# basic.net
KiCad netlist of a schematic drawn in EAGLE
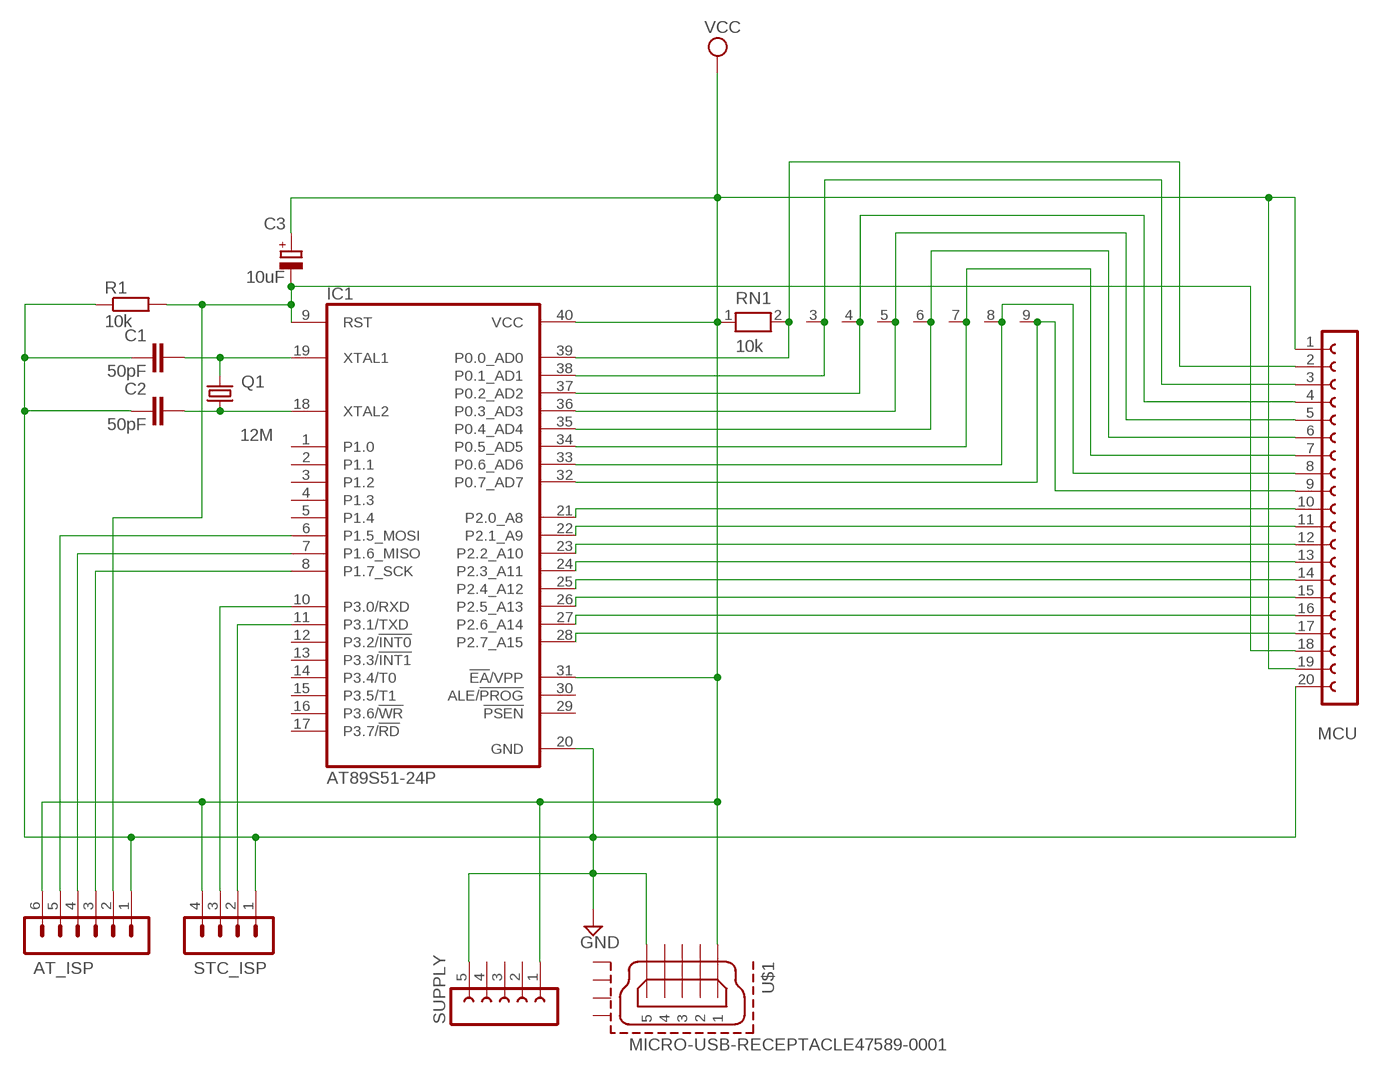
[diagram p0: schematic, sheet 1]

(export (version "E")
  (design (tool "Eeschema 10.0.6"))
  (components
    (comp (ref "AT_ISP")
      (value "MA06-1")
      (footprint "eagle-import:MA06-1")
      (libsource (lib "eagle-import") (part "MA06-1"))
    )
    (comp (ref "C1")
      (value "50pF")
      (footprint "eagle-import:C050-025X075")
      (libsource (lib "eagle-import") (part "C-EU050-025X075"))
    )
    (comp (ref "C2")
      (value "50pF")
      (footprint "eagle-import:C050-025X075")
      (libsource (lib "eagle-import") (part "C-EU050-025X075"))
    )
    (comp (ref "C3")
      (value "10uF")
      (footprint "eagle-import:E2,5-6")
      (libsource (lib "eagle-import") (part "CPOL-EUE2.5-6"))
    )
    (comp (ref "IC1")
      (value "AT89S51-24P")
      (footprint "eagle-import:DIL40")
      (fields (field (name "MPN") "AT89S51-24PU"))
      (libsource (lib "eagle-import") (part "AT89S51-P24"))
    )
    (comp (ref "MCU")
      (value "FE20-1")
      (footprint "eagle-import:FE20")
      (libsource (lib "eagle-import") (part "FE20-1"))
    )
    (comp (ref "Q1")
      (value "12M")
      (footprint "eagle-import:HC49U70")
      (libsource (lib "eagle-import") (part "CRYSTALHC49U70"))
    )
    (comp (ref "R1")
      (value "10k")
      (footprint "eagle-import:0207_10")
      (libsource (lib "eagle-import") (part "R-EU_0207/10"))
    )
    (comp (ref "RN1")
      (value "10k")
      (footprint "eagle-import:RN-9")
      (libsource (lib "eagle-import") (part "RN08"))
    )
    (comp (ref "STC_ISP")
      (value "MA04-1")
      (footprint "eagle-import:MA04-1")
      (libsource (lib "eagle-import") (part "MA04-1"))
    )
    (comp (ref "SUPPLY")
      (value "FE05-1")
      (footprint "eagle-import:FE05-1")
      (libsource (lib "eagle-import") (part "FE05-1"))
    )
    (comp (ref "U$1")
      (value "MICRO-USB-RECEPTACLE47589-0001")
      (footprint "eagle-import:47589-0001")
      (libsource (lib "eagle-import") (part "MICRO-USB-RECEPTACLE47589-0001"))
    )
  )
  (nets
    (net (code "1") (name "GND") (class "Default")
      (node (ref "AT_ISP") (pin "1") (pinfunction "1_1") (pintype "passive"))
      (node (ref "C1") (pin "1") (pinfunction "1_1") (pintype "passive"))
      (node (ref "C2") (pin "1") (pinfunction "1_1") (pintype "passive"))
      (node (ref "IC1") (pin "20") (pinfunction "GND_20") (pintype "power_in"))
      (node (ref "MCU") (pin "20") (pinfunction "20_20") (pintype "passive"))
      (node (ref "R1") (pin "1") (pinfunction "1_1") (pintype "passive"))
      (node (ref "STC_ISP") (pin "1") (pinfunction "1_1") (pintype "passive"))
      (node (ref "SUPPLY") (pin "5") (pinfunction "5_5") (pintype "passive"))
      (node (ref "U$1") (pin "5") (pinfunction "5_5") (pintype "input"))
    )
    (net (code "2") (name "Net-(IC1-P0.0_AD0)") (class "Default")
      (node (ref "IC1") (pin "39") (pinfunction "P0.0_AD0_39") (pintype "bidirectional"))
      (node (ref "MCU") (pin "2") (pinfunction "2_2") (pintype "passive"))
      (node (ref "RN1") (pin "2") (pinfunction "2_2") (pintype "passive"))
    )
    (net (code "3") (name "Net-(IC1-P0.1_AD1)") (class "Default")
      (node (ref "IC1") (pin "38") (pinfunction "P0.1_AD1_38") (pintype "bidirectional"))
      (node (ref "MCU") (pin "3") (pinfunction "3_3") (pintype "passive"))
      (node (ref "RN1") (pin "3") (pinfunction "3_3") (pintype "passive"))
    )
    (net (code "4") (name "Net-(IC1-P0.2_AD2)") (class "Default")
      (node (ref "IC1") (pin "37") (pinfunction "P0.2_AD2_37") (pintype "bidirectional"))
      (node (ref "MCU") (pin "4") (pinfunction "4_4") (pintype "passive"))
      (node (ref "RN1") (pin "4") (pinfunction "4_4") (pintype "passive"))
    )
    (net (code "5") (name "Net-(IC1-P0.3_AD3)") (class "Default")
      (node (ref "IC1") (pin "36") (pinfunction "P0.3_AD3_36") (pintype "bidirectional"))
      (node (ref "MCU") (pin "5") (pinfunction "5_5") (pintype "passive"))
      (node (ref "RN1") (pin "5") (pinfunction "5_5") (pintype "passive"))
    )
    (net (code "6") (name "Net-(IC1-P0.4_AD4)") (class "Default")
      (node (ref "IC1") (pin "35") (pinfunction "P0.4_AD4_35") (pintype "bidirectional"))
      (node (ref "MCU") (pin "6") (pinfunction "6_6") (pintype "passive"))
      (node (ref "RN1") (pin "6") (pinfunction "6_6") (pintype "passive"))
    )
    (net (code "7") (name "Net-(IC1-P0.5_AD5)") (class "Default")
      (node (ref "IC1") (pin "34") (pinfunction "P0.5_AD5_34") (pintype "bidirectional"))
      (node (ref "MCU") (pin "7") (pinfunction "7_7") (pintype "passive"))
      (node (ref "RN1") (pin "7") (pinfunction "7_7") (pintype "passive"))
    )
    (net (code "8") (name "Net-(IC1-P0.6_AD6)") (class "Default")
      (node (ref "IC1") (pin "33") (pinfunction "P0.6_AD6_33") (pintype "bidirectional"))
      (node (ref "MCU") (pin "8") (pinfunction "8_8") (pintype "passive"))
      (node (ref "RN1") (pin "8") (pinfunction "8_8") (pintype "passive"))
    )
    (net (code "9") (name "Net-(IC1-P0.7_AD7)") (class "Default")
      (node (ref "IC1") (pin "32") (pinfunction "P0.7_AD7_32") (pintype "bidirectional"))
      (node (ref "MCU") (pin "9") (pinfunction "9_9") (pintype "passive"))
      (node (ref "RN1") (pin "9") (pinfunction "9_9") (pintype "passive"))
    )
    (net (code "10") (name "Net-(IC1-P1.5_MOSI)") (class "Default")
      (node (ref "AT_ISP") (pin "5") (pinfunction "5_5") (pintype "passive"))
      (node (ref "IC1") (pin "6") (pinfunction "P1.5_MOSI_6") (pintype "bidirectional"))
    )
    (net (code "11") (name "Net-(IC1-P1.6_MISO)") (class "Default")
      (node (ref "AT_ISP") (pin "4") (pinfunction "4_4") (pintype "passive"))
      (node (ref "IC1") (pin "7") (pinfunction "P1.6_MISO_7") (pintype "bidirectional"))
    )
    (net (code "12") (name "Net-(IC1-P1.7_SCK)") (class "Default")
      (node (ref "AT_ISP") (pin "3") (pinfunction "3_3") (pintype "passive"))
      (node (ref "IC1") (pin "8") (pinfunction "P1.7_SCK_8") (pintype "bidirectional"))
    )
    (net (code "13") (name "Net-(IC1-P2.0_A8)") (class "Default")
      (node (ref "IC1") (pin "21") (pinfunction "P2.0_A8_21") (pintype "bidirectional"))
      (node (ref "MCU") (pin "10") (pinfunction "10_10") (pintype "passive"))
    )
    (net (code "14") (name "Net-(IC1-P2.1_A9)") (class "Default")
      (node (ref "IC1") (pin "22") (pinfunction "P2.1_A9_22") (pintype "bidirectional"))
      (node (ref "MCU") (pin "11") (pinfunction "11_11") (pintype "passive"))
    )
    (net (code "15") (name "Net-(IC1-P2.2_A10)") (class "Default")
      (node (ref "IC1") (pin "23") (pinfunction "P2.2_A10_23") (pintype "bidirectional"))
      (node (ref "MCU") (pin "12") (pinfunction "12_12") (pintype "passive"))
    )
    (net (code "16") (name "Net-(IC1-P2.3_A11)") (class "Default")
      (node (ref "IC1") (pin "24") (pinfunction "P2.3_A11_24") (pintype "bidirectional"))
      (node (ref "MCU") (pin "13") (pinfunction "13_13") (pintype "passive"))
    )
    (net (code "17") (name "Net-(IC1-P2.4_A12)") (class "Default")
      (node (ref "IC1") (pin "25") (pinfunction "P2.4_A12_25") (pintype "bidirectional"))
      (node (ref "MCU") (pin "14") (pinfunction "14_14") (pintype "passive"))
    )
    (net (code "18") (name "Net-(IC1-P2.5_A13)") (class "Default")
      (node (ref "IC1") (pin "26") (pinfunction "P2.5_A13_26") (pintype "bidirectional"))
      (node (ref "MCU") (pin "15") (pinfunction "15_15") (pintype "passive"))
    )
    (net (code "19") (name "Net-(IC1-P2.6_A14)") (class "Default")
      (node (ref "IC1") (pin "27") (pinfunction "P2.6_A14_27") (pintype "bidirectional"))
      (node (ref "MCU") (pin "16") (pinfunction "16_16") (pintype "passive"))
    )
    (net (code "20") (name "Net-(IC1-P2.7_A15)") (class "Default")
      (node (ref "IC1") (pin "28") (pinfunction "P2.7_A15_28") (pintype "bidirectional"))
      (node (ref "MCU") (pin "17") (pinfunction "17_17") (pintype "passive"))
    )
    (net (code "21") (name "Net-(IC1-P3.0{slash}RXD)") (class "Default")
      (node (ref "IC1") (pin "10") (pinfunction "P3.0/RXD_10") (pintype "bidirectional"))
      (node (ref "STC_ISP") (pin "3") (pinfunction "3_3") (pintype "passive"))
    )
    (net (code "22") (name "Net-(IC1-P3.1{slash}TXD)") (class "Default")
      (node (ref "IC1") (pin "11") (pinfunction "P3.1/TXD_11") (pintype "bidirectional"))
      (node (ref "STC_ISP") (pin "2") (pinfunction "2_2") (pintype "passive"))
    )
    (net (code "23") (name "Net-(IC1-RST)") (class "Default")
      (node (ref "AT_ISP") (pin "2") (pinfunction "2_2") (pintype "passive"))
      (node (ref "C3") (pin "-") (pinfunction "-_-") (pintype "passive"))
      (node (ref "IC1") (pin "9") (pinfunction "RST_9") (pintype "input"))
      (node (ref "MCU") (pin "18") (pinfunction "18_18") (pintype "passive"))
      (node (ref "R1") (pin "2") (pinfunction "2_2") (pintype "passive"))
    )
    (net (code "24") (name "Net-(IC1-XTAL1)") (class "Default")
      (node (ref "C1") (pin "2") (pinfunction "2_2") (pintype "passive"))
      (node (ref "IC1") (pin "19") (pinfunction "XTAL1_19") (pintype "input"))
      (node (ref "Q1") (pin "2") (pinfunction "2_2") (pintype "passive"))
    )
    (net (code "25") (name "Net-(IC1-XTAL2)") (class "Default")
      (node (ref "C2") (pin "2") (pinfunction "2_2") (pintype "passive"))
      (node (ref "IC1") (pin "18") (pinfunction "XTAL2_18") (pintype "input"))
      (node (ref "Q1") (pin "1") (pinfunction "1_1") (pintype "passive"))
    )
    (net (code "26") (name "VCC") (class "Default")
      (node (ref "AT_ISP") (pin "6") (pinfunction "6_6") (pintype "passive"))
      (node (ref "C3") (pin "+") (pinfunction "+_+") (pintype "passive"))
      (node (ref "IC1") (pin "31") (pinfunction "~{EA}/VPP_31") (pintype "input"))
      (node (ref "IC1") (pin "40") (pinfunction "VCC_40") (pintype "power_in"))
      (node (ref "MCU") (pin "1") (pinfunction "1_1") (pintype "passive"))
      (node (ref "MCU") (pin "19") (pinfunction "19_19") (pintype "passive"))
      (node (ref "RN1") (pin "1") (pinfunction "1_1") (pintype "passive"))
      (node (ref "STC_ISP") (pin "4") (pinfunction "4_4") (pintype "passive"))
      (node (ref "SUPPLY") (pin "1") (pinfunction "1_1") (pintype "passive"))
      (node (ref "U$1") (pin "1") (pinfunction "1_1") (pintype "input"))
    )
    (net (code "27") (name "unconnected-(IC1-ALE{slash}~{PROG}-Pad30)") (class "Default")
      (node (ref "IC1") (pin "30") (pinfunction "ALE/~{PROG}_30") (pintype "output"))
    )
    (net (code "28") (name "unconnected-(IC1-P1.0-Pad1)") (class "Default")
      (node (ref "IC1") (pin "1") (pinfunction "P1.0_1") (pintype "bidirectional"))
    )
    (net (code "29") (name "unconnected-(IC1-P1.1-Pad2)") (class "Default")
      (node (ref "IC1") (pin "2") (pinfunction "P1.1_2") (pintype "bidirectional"))
    )
    (net (code "30") (name "unconnected-(IC1-P1.2-Pad3)") (class "Default")
      (node (ref "IC1") (pin "3") (pinfunction "P1.2_3") (pintype "bidirectional"))
    )
    (net (code "31") (name "unconnected-(IC1-P1.3-Pad4)") (class "Default")
      (node (ref "IC1") (pin "4") (pinfunction "P1.3_4") (pintype "bidirectional"))
    )
    (net (code "32") (name "unconnected-(IC1-P1.4-Pad5)") (class "Default")
      (node (ref "IC1") (pin "5") (pinfunction "P1.4_5") (pintype "bidirectional"))
    )
    (net (code "33") (name "unconnected-(IC1-P3.2{slash}~{INT0}-Pad12)") (class "Default")
      (node (ref "IC1") (pin "12") (pinfunction "P3.2/~{INT0}_12") (pintype "bidirectional"))
    )
    (net (code "34") (name "unconnected-(IC1-P3.3{slash}~{INT1}-Pad13)") (class "Default")
      (node (ref "IC1") (pin "13") (pinfunction "P3.3/~{INT1}_13") (pintype "bidirectional"))
    )
    (net (code "35") (name "unconnected-(IC1-P3.4{slash}T0-Pad14)") (class "Default")
      (node (ref "IC1") (pin "14") (pinfunction "P3.4/T0_14") (pintype "bidirectional"))
    )
    (net (code "36") (name "unconnected-(IC1-P3.5{slash}T1-Pad15)") (class "Default")
      (node (ref "IC1") (pin "15") (pinfunction "P3.5/T1_15") (pintype "bidirectional"))
    )
    (net (code "37") (name "unconnected-(IC1-P3.6{slash}~{WR}-Pad16)") (class "Default")
      (node (ref "IC1") (pin "16") (pinfunction "P3.6/~{WR}_16") (pintype "bidirectional"))
    )
    (net (code "38") (name "unconnected-(IC1-P3.7{slash}~{RD}-Pad17)") (class "Default")
      (node (ref "IC1") (pin "17") (pinfunction "P3.7/~{RD}_17") (pintype "bidirectional"))
    )
    (net (code "39") (name "unconnected-(IC1-~{PSEN}-Pad29)") (class "Default")
      (node (ref "IC1") (pin "29") (pinfunction "~{PSEN}_29") (pintype "output"))
    )
    (net (code "40") (name "unconnected-(SUPPLY-Pad2)") (class "Default")
      (node (ref "SUPPLY") (pin "2") (pinfunction "2_2") (pintype "passive"))
    )
    (net (code "41") (name "unconnected-(SUPPLY-Pad3)") (class "Default")
      (node (ref "SUPPLY") (pin "3") (pinfunction "3_3") (pintype "passive"))
    )
    (net (code "42") (name "unconnected-(SUPPLY-Pad4)") (class "Default")
      (node (ref "SUPPLY") (pin "4") (pinfunction "4_4") (pintype "passive"))
    )
    (net (code "43") (name "unconnected-(U$1-GND1-PadCASING1)") (class "Default")
      (node (ref "U$1") (pin "CASING1") (pinfunction "GND1_CASING1") (pintype "bidirectional"))
    )
    (net (code "44") (name "unconnected-(U$1-GND2-PadCASING2)") (class "Default")
      (node (ref "U$1") (pin "CASING2") (pinfunction "GND2_CASING2") (pintype "bidirectional"))
    )
    (net (code "45") (name "unconnected-(U$1-GND3-PadCASING3)") (class "Default")
      (node (ref "U$1") (pin "CASING3") (pinfunction "GND3_CASING3") (pintype "bidirectional"))
    )
    (net (code "46") (name "unconnected-(U$1-GND4-PadCASING4)") (class "Default")
      (node (ref "U$1") (pin "CASING4") (pinfunction "GND4_CASING4") (pintype "bidirectional"))
    )
    (net (code "47") (name "unconnected-(U$1-Pad2)") (class "Default")
      (node (ref "U$1") (pin "2") (pinfunction "2_2") (pintype "input"))
    )
    (net (code "48") (name "unconnected-(U$1-Pad3)") (class "Default")
      (node (ref "U$1") (pin "3") (pinfunction "3_3") (pintype "input"))
    )
    (net (code "49") (name "unconnected-(U$1-Pad4)") (class "Default")
      (node (ref "U$1") (pin "4") (pinfunction "4_4") (pintype "input"))
    )
  )
)
